# SCH_STM8-__2022-05-08.net
KiCad netlist of a schematic drawn in EasyEDA
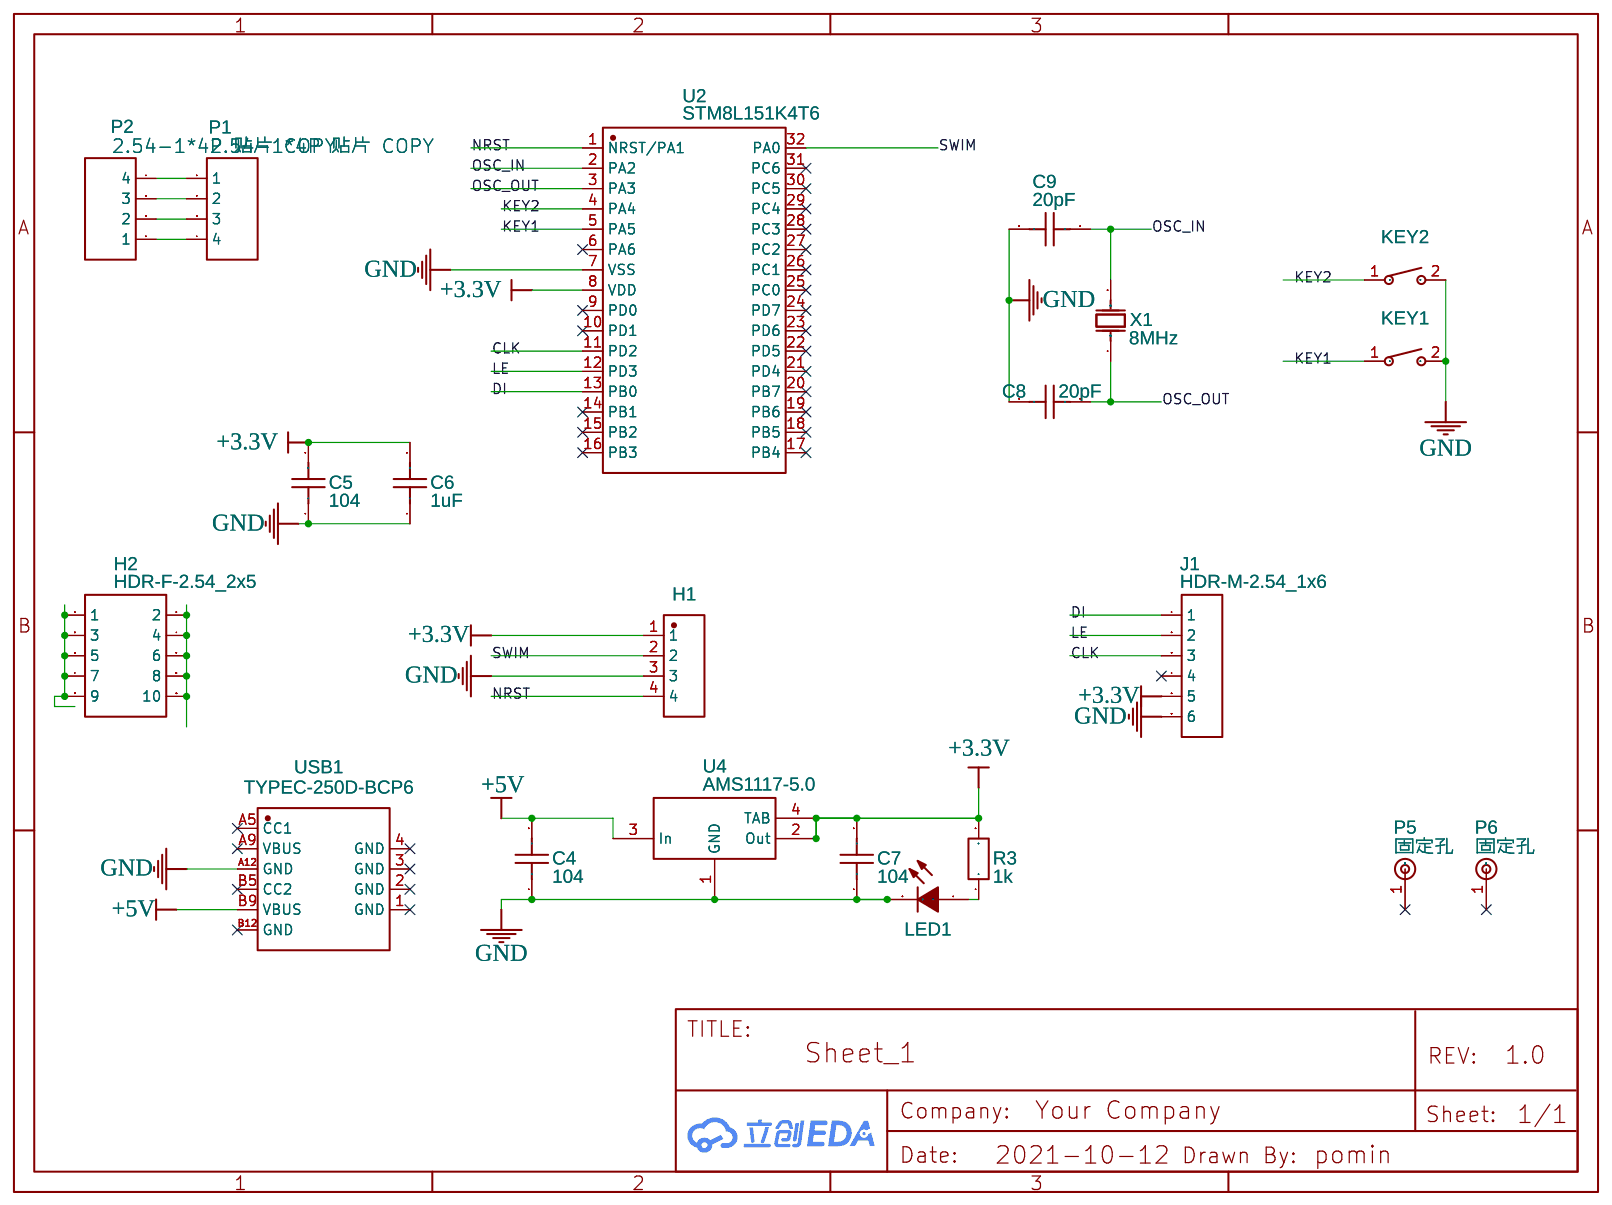
[diagram p0: schematic sheet]

(export (version "E")
  (design (tool "Eeschema 10.0.6"))
  (components
    (comp (ref "C4") (value "104") (libsource (lib "") (part "C_0805_US")))
    (comp (ref "C5")
      (value "104")
      (fields
        (field (name "BOM_Manufacturer Part") "CC0805JRX7R9BB563")
        (field (name "BOM_Supplier Part") "C520045")
      )
      (libsource (lib "") (part "CC0805JRX7R9BB563"))
    )
    (comp (ref "C6")
      (value "1uF")
      (fields
        (field (name "BOM_Manufacturer Part") "CC0805JRX7R9BB563")
        (field (name "BOM_Supplier Part") "C520045")
      )
      (libsource (lib "") (part "CC0805JRX7R9BB563"))
    )
    (comp (ref "C7") (value "104") (libsource (lib "") (part "C_0805_US")))
    (comp (ref "C8") (value "20pF") (libsource (lib "") (part "C_0603_US")))
    (comp (ref "C9") (value "20pF") (libsource (lib "") (part "C_0603_US")))
    (comp (ref "H1")
      (value "2.54-1*4P母")
      (fields (field (name "BOM_Supplier Part") "C2718488"))
      (libsource (lib "") (part "2.54-1*4P母"))
    )
    (comp (ref "H2")
      (value "HDR-F-2.54_2x5")
      (fields (field (name "BOM_Supplier Part") "C30419"))
      (libsource (lib "") (part "HDR-F-2.54_2x5"))
    )
    (comp (ref "J1")
      (value "HDR-M-2.54_1x6")
      (fields (field (name "BOM_Supplier Part") "C190819"))
      (libsource (lib "") (part "HDR-M-2.54_1x6"))
    )
    (comp (ref "KEY1")
      (value "UK-B0227-G4.3-160-W-JZ")
      (fields (field (name "BOM_Supplier Part") "C620345"))
      (libsource (lib "") (part "UK-B0227-G4.3-160-W-JZ"))
    )
    (comp (ref "KEY2")
      (value "UK-B0227-G4.3-160-W-JZ")
      (fields (field (name "BOM_Supplier Part") "C620345"))
      (libsource (lib "") (part "UK-B0227-G4.3-160-W-JZ"))
    )
    (comp (ref "LED1")
      (value "17-21SURC/S530-A3/TR8")
      (fields (field (name "BOM_Supplier Part") "C72037"))
      (libsource (lib "") (part "17-21SURC/S530-A3/TR8"))
    )
    (comp (ref "P1")
      (value "2.54-1*4P 贴片 COPY")
      (fields (field (name "BOM_Manufacturer Part") "2.54-1*4P") (field (name "BOM_Supplier Part") "C52709"))
      (libsource (lib "") (part "2.54-1*4P 贴片 COPY"))
    )
    (comp (ref "P2")
      (value "2.54-1*4P 贴片 COPY")
      (fields (field (name "BOM_Manufacturer Part") "2.54-1*4P") (field (name "BOM_Supplier Part") "C52709"))
      (libsource (lib "") (part "2.54-1*4P 贴片 COPY_1"))
    )
    (comp (ref "P5") (value "固定孔") (libsource (lib "") (part "固定孔")))
    (comp (ref "P6") (value "固定孔") (libsource (lib "") (part "固定孔")))
    (comp (ref "R3") (value "1k") (libsource (lib "") (part "R_0201_EU")))
    (comp (ref "U2")
      (value "STM8L151K4T6")
      (fields (field (name "BOM_Supplier Part") "C18719"))
      (libsource (lib "") (part "STM8L151K4T6"))
    )
    (comp (ref "U4")
      (value "AMS1117-5.0")
      (fields (field (name "BOM_Supplier Part") "C6187"))
      (libsource (lib "") (part "AMS1117-5.0"))
    )
    (comp (ref "USB1")
      (value "TYPEC-250D-BCP6")
      (fields (field (name "BOM_Supplier Part") "C720626"))
      (libsource (lib "") (part "TYPEC-250D-BCP6"))
    )
    (comp (ref "X1")
      (value "8MHz")
      (fields
        (field (name "BOM_Manufacturer Part") "9C1105LCSC-AAK2S")
        (field (name "BOM_Supplier Part") "C90938")
      )
      (libsource (lib "") (part "9C1105LCSC-AAK2S"))
    )
  )
  (nets
    (net (code "1") (name "+3.3V") (class "Default")
      (node (ref "C5") (pin "2") (pinfunction "2_2") (pintype "unspecified"))
      (node (ref "C6") (pin "2") (pinfunction "2_2") (pintype "unspecified"))
      (node (ref "C7") (pin "2") (pinfunction "2_2") (pintype "unspecified"))
      (node (ref "H1") (pin "1") (pinfunction "1_1") (pintype "unspecified"))
      (node (ref "J1") (pin "5") (pinfunction "5_5") (pintype "input"))
      (node (ref "R3") (pin "2") (pinfunction "2_2") (pintype "unspecified"))
      (node (ref "U2") (pin "8") (pinfunction "VDD_8") (pintype "unspecified"))
      (node (ref "U4") (pin "2") (pinfunction "Out_2") (pintype "unspecified"))
      (node (ref "U4") (pin "4") (pinfunction "TAB_4") (pintype "unspecified"))
    )
    (net (code "2") (name "+5V") (class "Default")
      (node (ref "C4") (pin "2") (pinfunction "2_2") (pintype "unspecified"))
      (node (ref "U4") (pin "3") (pinfunction "In_3") (pintype "unspecified"))
      (node (ref "USB1") (pin "B9") (pinfunction "VBUS_B9") (pintype "unspecified"))
    )
    (net (code "3") (name "/CLK") (class "Default")
      (node (ref "J1") (pin "3") (pinfunction "3_3") (pintype "input"))
      (node (ref "U2") (pin "11") (pinfunction "PD2_11") (pintype "unspecified"))
    )
    (net (code "4") (name "/DI") (class "Default")
      (node (ref "J1") (pin "1") (pinfunction "1_1") (pintype "input"))
      (node (ref "U2") (pin "13") (pinfunction "PB0_13") (pintype "unspecified"))
    )
    (net (code "5") (name "/KEY1") (class "Default")
      (node (ref "KEY1") (pin "1") (pinfunction "1_1") (pintype "unspecified"))
      (node (ref "U2") (pin "5") (pinfunction "PA5_5") (pintype "unspecified"))
    )
    (net (code "6") (name "/KEY2") (class "Default")
      (node (ref "KEY2") (pin "1") (pinfunction "1_1") (pintype "unspecified"))
      (node (ref "U2") (pin "4") (pinfunction "PA4_4") (pintype "unspecified"))
    )
    (net (code "7") (name "/LE") (class "Default")
      (node (ref "J1") (pin "2") (pinfunction "2_2") (pintype "input"))
      (node (ref "U2") (pin "12") (pinfunction "PD3_12") (pintype "unspecified"))
    )
    (net (code "8") (name "/NRST") (class "Default")
      (node (ref "H1") (pin "4") (pinfunction "4_4") (pintype "unspecified"))
      (node (ref "U2") (pin "1") (pinfunction "NRST/PA1_1") (pintype "unspecified"))
    )
    (net (code "9") (name "/OSC_IN") (class "Default")
      (node (ref "C9") (pin "1") (pinfunction "1_1") (pintype "unspecified"))
      (node (ref "U2") (pin "2") (pinfunction "PA2_2") (pintype "unspecified"))
      (node (ref "X1") (pin "2") (pinfunction "OSC2_2") (pintype "input"))
    )
    (net (code "10") (name "/OSC_OUT") (class "Default")
      (node (ref "C8") (pin "1") (pinfunction "1_1") (pintype "unspecified"))
      (node (ref "U2") (pin "3") (pinfunction "PA3_3") (pintype "unspecified"))
      (node (ref "X1") (pin "1") (pinfunction "OSC1_1") (pintype "input"))
    )
    (net (code "11") (name "/SWIM") (class "Default")
      (node (ref "H1") (pin "2") (pinfunction "2_2") (pintype "unspecified"))
      (node (ref "U2") (pin "32") (pinfunction "PA0_32") (pintype "unspecified"))
    )
    (net (code "12") (name "GND") (class "Default")
      (node (ref "C4") (pin "1") (pinfunction "1_1") (pintype "unspecified"))
      (node (ref "C5") (pin "1") (pinfunction "1_1") (pintype "unspecified"))
      (node (ref "C6") (pin "1") (pinfunction "1_1") (pintype "unspecified"))
      (node (ref "C7") (pin "1") (pinfunction "1_1") (pintype "unspecified"))
      (node (ref "C8") (pin "2") (pinfunction "2_2") (pintype "unspecified"))
      (node (ref "C9") (pin "2") (pinfunction "2_2") (pintype "unspecified"))
      (node (ref "H1") (pin "3") (pinfunction "3_3") (pintype "unspecified"))
      (node (ref "J1") (pin "6") (pinfunction "6_6") (pintype "input"))
      (node (ref "KEY1") (pin "2") (pinfunction "2_2") (pintype "unspecified"))
      (node (ref "KEY2") (pin "2") (pinfunction "2_2") (pintype "unspecified"))
      (node (ref "LED1") (pin "2") (pinfunction "C_2") (pintype "input"))
      (node (ref "U2") (pin "7") (pinfunction "VSS_7") (pintype "unspecified"))
      (node (ref "U4") (pin "1") (pinfunction "GND_1") (pintype "unspecified"))
      (node (ref "USB1") (pin "A12") (pinfunction "GND_A12") (pintype "unspecified"))
    )
    (net (code "13") (name "Net-(H2-Pad1)") (class "Default")
      (node (ref "H2") (pin "1") (pinfunction "1_1") (pintype "unspecified"))
      (node (ref "H2") (pin "3") (pinfunction "3_3") (pintype "unspecified"))
      (node (ref "H2") (pin "5") (pinfunction "5_5") (pintype "unspecified"))
      (node (ref "H2") (pin "7") (pinfunction "7_7") (pintype "unspecified"))
      (node (ref "H2") (pin "9") (pinfunction "9_9") (pintype "unspecified"))
    )
    (net (code "14") (name "Net-(H2-Pad10)") (class "Default")
      (node (ref "H2") (pin "10") (pinfunction "10_10") (pintype "unspecified"))
      (node (ref "H2") (pin "2") (pinfunction "2_2") (pintype "unspecified"))
      (node (ref "H2") (pin "4") (pinfunction "4_4") (pintype "unspecified"))
      (node (ref "H2") (pin "6") (pinfunction "6_6") (pintype "unspecified"))
      (node (ref "H2") (pin "8") (pinfunction "8_8") (pintype "unspecified"))
    )
    (net (code "15") (name "Net-(LED1-A)") (class "Default")
      (node (ref "LED1") (pin "1") (pinfunction "A_1") (pintype "input"))
      (node (ref "R3") (pin "1") (pinfunction "1_1") (pintype "unspecified"))
    )
    (net (code "16") (name "Net-(P1-Pad1)") (class "Default")
      (node (ref "P1") (pin "1") (pinfunction "1_1") (pintype "input"))
      (node (ref "P2") (pin "4") (pinfunction "4_4") (pintype "input"))
    )
    (net (code "17") (name "Net-(P1-Pad2)") (class "Default")
      (node (ref "P1") (pin "2") (pinfunction "2_2") (pintype "input"))
      (node (ref "P2") (pin "3") (pinfunction "3_3") (pintype "input"))
    )
    (net (code "18") (name "Net-(P1-Pad3)") (class "Default")
      (node (ref "P1") (pin "3") (pinfunction "3_3") (pintype "input"))
      (node (ref "P2") (pin "2") (pinfunction "2_2") (pintype "input"))
    )
    (net (code "19") (name "Net-(P1-Pad4)") (class "Default")
      (node (ref "P1") (pin "4") (pinfunction "4_4") (pintype "input"))
      (node (ref "P2") (pin "1") (pinfunction "1_1") (pintype "input"))
    )
    (net (code "20") (name "unconnected-(J1-Pad4)") (class "Default")
      (node (ref "J1") (pin "4") (pinfunction "4_4") (pintype "input+no_connect"))
    )
    (net (code "21") (name "unconnected-(P5-3mm洞-Pad1)") (class "Default")
      (node (ref "P5") (pin "1") (pinfunction "3mm洞_1") (pintype "unspecified+no_connect"))
    )
    (net (code "22") (name "unconnected-(P6-3mm洞-Pad1)") (class "Default")
      (node (ref "P6") (pin "1") (pinfunction "3mm洞_1") (pintype "unspecified+no_connect"))
    )
    (net (code "23") (name "unconnected-(U2-PA6-Pad6)") (class "Default")
      (node (ref "U2") (pin "6") (pinfunction "PA6_6") (pintype "unspecified+no_connect"))
    )
    (net (code "24") (name "unconnected-(U2-PB1-Pad14)") (class "Default")
      (node (ref "U2") (pin "14") (pinfunction "PB1_14") (pintype "unspecified+no_connect"))
    )
    (net (code "25") (name "unconnected-(U2-PB2-Pad15)") (class "Default")
      (node (ref "U2") (pin "15") (pinfunction "PB2_15") (pintype "unspecified+no_connect"))
    )
    (net (code "26") (name "unconnected-(U2-PB3-Pad16)") (class "Default")
      (node (ref "U2") (pin "16") (pinfunction "PB3_16") (pintype "unspecified+no_connect"))
    )
    (net (code "27") (name "unconnected-(U2-PB4-Pad17)") (class "Default")
      (node (ref "U2") (pin "17") (pinfunction "PB4_17") (pintype "unspecified+no_connect"))
    )
    (net (code "28") (name "unconnected-(U2-PB5-Pad18)") (class "Default")
      (node (ref "U2") (pin "18") (pinfunction "PB5_18") (pintype "unspecified+no_connect"))
    )
    (net (code "29") (name "unconnected-(U2-PB6-Pad19)") (class "Default")
      (node (ref "U2") (pin "19") (pinfunction "PB6_19") (pintype "unspecified+no_connect"))
    )
    (net (code "30") (name "unconnected-(U2-PB7-Pad20)") (class "Default")
      (node (ref "U2") (pin "20") (pinfunction "PB7_20") (pintype "unspecified+no_connect"))
    )
    (net (code "31") (name "unconnected-(U2-PC0-Pad25)") (class "Default")
      (node (ref "U2") (pin "25") (pinfunction "PC0_25") (pintype "unspecified+no_connect"))
    )
    (net (code "32") (name "unconnected-(U2-PC1-Pad26)") (class "Default")
      (node (ref "U2") (pin "26") (pinfunction "PC1_26") (pintype "unspecified+no_connect"))
    )
    (net (code "33") (name "unconnected-(U2-PC2-Pad27)") (class "Default")
      (node (ref "U2") (pin "27") (pinfunction "PC2_27") (pintype "unspecified+no_connect"))
    )
    (net (code "34") (name "unconnected-(U2-PC3-Pad28)") (class "Default")
      (node (ref "U2") (pin "28") (pinfunction "PC3_28") (pintype "unspecified+no_connect"))
    )
    (net (code "35") (name "unconnected-(U2-PC4-Pad29)") (class "Default")
      (node (ref "U2") (pin "29") (pinfunction "PC4_29") (pintype "unspecified+no_connect"))
    )
    (net (code "36") (name "unconnected-(U2-PC5-Pad30)") (class "Default")
      (node (ref "U2") (pin "30") (pinfunction "PC5_30") (pintype "unspecified+no_connect"))
    )
    (net (code "37") (name "unconnected-(U2-PC6-Pad31)") (class "Default")
      (node (ref "U2") (pin "31") (pinfunction "PC6_31") (pintype "unspecified+no_connect"))
    )
    (net (code "38") (name "unconnected-(U2-PD0-Pad9)") (class "Default")
      (node (ref "U2") (pin "9") (pinfunction "PD0_9") (pintype "unspecified+no_connect"))
    )
    (net (code "39") (name "unconnected-(U2-PD1-Pad10)") (class "Default")
      (node (ref "U2") (pin "10") (pinfunction "PD1_10") (pintype "unspecified+no_connect"))
    )
    (net (code "40") (name "unconnected-(U2-PD4-Pad21)") (class "Default")
      (node (ref "U2") (pin "21") (pinfunction "PD4_21") (pintype "unspecified+no_connect"))
    )
    (net (code "41") (name "unconnected-(U2-PD5-Pad22)") (class "Default")
      (node (ref "U2") (pin "22") (pinfunction "PD5_22") (pintype "unspecified+no_connect"))
    )
    (net (code "42") (name "unconnected-(U2-PD6-Pad23)") (class "Default")
      (node (ref "U2") (pin "23") (pinfunction "PD6_23") (pintype "unspecified+no_connect"))
    )
    (net (code "43") (name "unconnected-(U2-PD7-Pad24)") (class "Default")
      (node (ref "U2") (pin "24") (pinfunction "PD7_24") (pintype "unspecified+no_connect"))
    )
    (net (code "44") (name "unconnected-(USB1-CC1-PadA5)") (class "Default")
      (node (ref "USB1") (pin "A5") (pinfunction "CC1_A5") (pintype "unspecified+no_connect"))
    )
    (net (code "45") (name "unconnected-(USB1-CC2-PadB5)") (class "Default")
      (node (ref "USB1") (pin "B5") (pinfunction "CC2_B5") (pintype "unspecified+no_connect"))
    )
    (net (code "46") (name "unconnected-(USB1-GND-Pad1)") (class "Default")
      (node (ref "USB1") (pin "1") (pinfunction "GND_1") (pintype "unspecified+no_connect"))
    )
    (net (code "47") (name "unconnected-(USB1-GND-Pad2)") (class "Default")
      (node (ref "USB1") (pin "2") (pinfunction "GND_2") (pintype "unspecified+no_connect"))
    )
    (net (code "48") (name "unconnected-(USB1-GND-Pad3)") (class "Default")
      (node (ref "USB1") (pin "3") (pinfunction "GND_3") (pintype "unspecified+no_connect"))
    )
    (net (code "49") (name "unconnected-(USB1-GND-Pad4)") (class "Default")
      (node (ref "USB1") (pin "4") (pinfunction "GND_4") (pintype "unspecified+no_connect"))
    )
    (net (code "50") (name "unconnected-(USB1-GND-PadB12)") (class "Default")
      (node (ref "USB1") (pin "B12") (pinfunction "GND_B12") (pintype "unspecified+no_connect"))
    )
    (net (code "51") (name "unconnected-(USB1-VBUS-PadA9)") (class "Default")
      (node (ref "USB1") (pin "A9") (pinfunction "VBUS_A9") (pintype "unspecified+no_connect"))
    )
  )
)
